# tiny.net
KiCad netlist of a schematic drawn in EAGLE
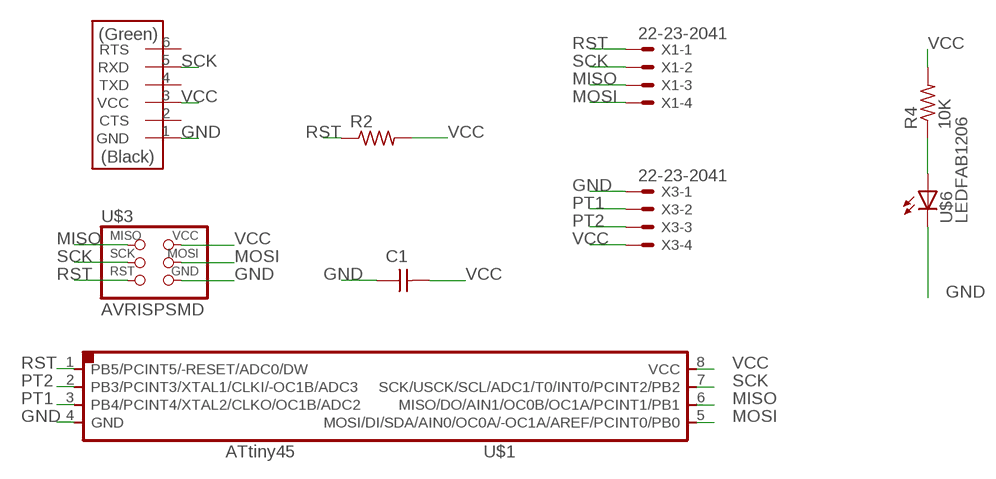
[diagram p0: schematic, sheet 1]

(export (version "E")
  (design (tool "Eeschema 10.0.6"))
  (components
    (comp (ref "C1")
      (value "CAP-UNPOLARIZEDFAB")
      (footprint "eagle-import:C1206FAB")
      (libsource (lib "eagle-import") (part "CAP-UNPOLARIZEDFAB"))
    )
    (comp (ref "R2")
      (value "RES-US1206FAB")
      (footprint "eagle-import:R1206FAB")
      (libsource (lib "eagle-import") (part "RES-US1206FAB"))
    )
    (comp (ref "R4")
      (value "10K")
      (footprint "eagle-import:R1206FAB")
      (libsource (lib "eagle-import") (part "RES-US1206FAB"))
    )
    (comp (ref "U$1")
      (value "ATTINY45SI")
      (footprint "eagle-import:SOIC8")
      (libsource (lib "eagle-import") (part "ATTINY45SI"))
    )
    (comp (ref "U$3")
      (value "AVRISPSMD")
      (footprint "eagle-import:2X03SMD")
      (libsource (lib "eagle-import") (part "AVRISPSMD"))
    )
    (comp (ref "U$4")
      (value "FTDI-SMD-HEADER")
      (footprint "eagle-import:1X06SMD")
      (libsource (lib "eagle-import") (part "FTDI-SMD-HEADER"))
    )
    (comp (ref "U$6")
      (value "LEDFAB1206")
      (footprint "eagle-import:LED1206FAB")
      (libsource (lib "eagle-import") (part "LEDFAB1206"))
    )
    (comp (ref "X1")
      (value "22-23-2041")
      (footprint "eagle-import:22-23-2041")
      (fields (field (name "MF") "MOLEX"))
      (libsource (lib "eagle-import") (part "22-23-2041"))
    )
    (comp (ref "X3")
      (value "22-23-2041")
      (footprint "eagle-import:22-23-2041")
      (fields (field (name "MF") "MOLEX"))
      (libsource (lib "eagle-import") (part "22-23-2041"))
    )
  )
  (nets
    (net (code "1") (name "/GND") (class "Default")
      (node (ref "C1") (pin "1") (pinfunction "1_1") (pintype "passive"))
      (node (ref "U$1") (pin "4") (pinfunction "GND_4") (pintype "bidirectional"))
      (node (ref "U$3") (pin "6") (pinfunction "GND_6") (pintype "passive"))
      (node (ref "U$4") (pin "1") (pinfunction "GND_1") (pintype "bidirectional"))
      (node (ref "U$6") (pin "2") (pinfunction "C_2") (pintype "passive"))
      (node (ref "X3") (pin "1") (pinfunction "S_1") (pintype "passive"))
    )
    (net (code "2") (name "/MISO") (class "Default")
      (node (ref "U$1") (pin "6") (pinfunction "MISO/DO/AIN1/OC0B/OC1A/PCINT1/PB1_6") (pintype "bidirectional"))
      (node (ref "U$3") (pin "1") (pinfunction "MISO_1") (pintype "passive"))
      (node (ref "X1") (pin "3") (pinfunction "S_3") (pintype "passive"))
    )
    (net (code "3") (name "/MOSI") (class "Default")
      (node (ref "U$1") (pin "5") (pinfunction "MOSI/DI/SDA/AIN0/OC0A/-OC1A/AREF/PCINT0/PB0_5") (pintype "bidirectional"))
      (node (ref "U$3") (pin "4") (pinfunction "MOSI_4") (pintype "passive"))
      (node (ref "X1") (pin "4") (pinfunction "S_4") (pintype "passive"))
    )
    (net (code "4") (name "/PT1") (class "Default")
      (node (ref "U$1") (pin "3") (pinfunction "PB4/PCINT4/XTAL2/CLKO/OC1B/ADC2_3") (pintype "bidirectional"))
      (node (ref "X3") (pin "2") (pinfunction "S_2") (pintype "passive"))
    )
    (net (code "5") (name "/PT2") (class "Default")
      (node (ref "U$1") (pin "2") (pinfunction "PB3/PCINT3/XTAL1/CLKI/-OC1B/ADC3_2") (pintype "bidirectional"))
      (node (ref "X3") (pin "3") (pinfunction "S_3") (pintype "passive"))
    )
    (net (code "6") (name "/RST") (class "Default")
      (node (ref "R2") (pin "1") (pinfunction "1_1") (pintype "passive"))
      (node (ref "U$1") (pin "1") (pinfunction "PB5/PCINT5/-RESET/ADC0/DW_1") (pintype "bidirectional"))
      (node (ref "U$3") (pin "5") (pinfunction "RST_5") (pintype "passive"))
      (node (ref "X1") (pin "1") (pinfunction "S_1") (pintype "passive"))
    )
    (net (code "7") (name "/SCK") (class "Default")
      (node (ref "U$1") (pin "7") (pinfunction "SCK/USCK/SCL/ADC1/T0/INT0/PCINT2/PB2_7") (pintype "bidirectional"))
      (node (ref "U$3") (pin "3") (pinfunction "SCK_3") (pintype "passive"))
      (node (ref "U$4") (pin "5") (pinfunction "RXD_5") (pintype "bidirectional"))
      (node (ref "X1") (pin "2") (pinfunction "S_2") (pintype "passive"))
    )
    (net (code "8") (name "/VCC") (class "Default")
      (node (ref "C1") (pin "2") (pinfunction "2_2") (pintype "passive"))
      (node (ref "R2") (pin "2") (pinfunction "2_2") (pintype "passive"))
      (node (ref "R4") (pin "2") (pinfunction "2_2") (pintype "passive"))
      (node (ref "U$1") (pin "8") (pinfunction "VCC_8") (pintype "bidirectional"))
      (node (ref "U$3") (pin "2") (pinfunction "VCC_2") (pintype "passive"))
      (node (ref "U$4") (pin "3") (pinfunction "VCC_3") (pintype "bidirectional"))
      (node (ref "X3") (pin "4") (pinfunction "S_4") (pintype "passive"))
    )
    (net (code "9") (name "Net-(U$6-A)") (class "Default")
      (node (ref "R4") (pin "1") (pinfunction "1_1") (pintype "passive"))
      (node (ref "U$6") (pin "1") (pinfunction "A_1") (pintype "passive"))
    )
    (net (code "10") (name "unconnected-(U$4-CTS-Pad2)") (class "Default")
      (node (ref "U$4") (pin "2") (pinfunction "CTS_2") (pintype "bidirectional"))
    )
    (net (code "11") (name "unconnected-(U$4-RTS-Pad6)") (class "Default")
      (node (ref "U$4") (pin "6") (pinfunction "RTS_6") (pintype "bidirectional"))
    )
    (net (code "12") (name "unconnected-(U$4-TXD-Pad4)") (class "Default")
      (node (ref "U$4") (pin "4") (pinfunction "TXD_4") (pintype "bidirectional"))
    )
  )
)
